# Nguon3V.net
KiCad netlist of a schematic drawn in Altium Designer
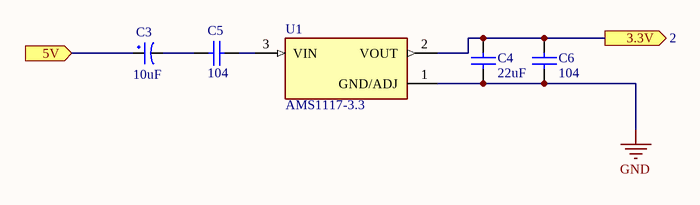
[diagram p0: Nguon3V.SchDoc]

(export (version "E")
  (design (tool "Eeschema 10.0.6"))
  (components
    (comp (ref "C3")
      (value "10uF")
      (footprint "tu hoa 4mm")
      (description "Cắm")
      (libsource (lib "Altium_Lib_by_KhueNguyenCreator") (part "Tu Hoa 10uF 16V 4x7"))
    )
    (comp (ref "C4")
      (value "22uF")
      (footprint "tu tantalum dip5.08")
      (description "Cắm")
      (libsource (lib "Altium_Lib_by_KhueNguyenCreator") (part "Tu tantalum 0.22uF 50V DIP5.08"))
    )
    (comp (ref "C5")
      (value "104")
      (footprint "tu gom")
      (description "Cắm")
      (libsource (lib "Altium_Lib_by_KhueNguyenCreator") (part "Tu gom 104 50V"))
    )
    (comp (ref "C6")
      (value "104")
      (footprint "tu gom")
      (description "Cắm")
      (libsource (lib "Altium_Lib_by_KhueNguyenCreator") (part "Tu gom 104 50V"))
    )
    (comp (ref "U1")
      (value "AMS1117-3.3")
      (footprint "SOT229P700X180-4N")
      (description "Sot223/Pkg 1-Amp 3.3-Volt Low Drop Out Voltage Regulatator")
      (fields (field (name "MF") "Advanced Monolithic Systems"))
      (libsource (lib "AMS1117-3.3") (part "AMS1117-3.3"))
    )
  )
  (nets
    (net (code "1") (name "/3.3V") (class "Default")
      (node (ref "C4") (pin "1") (pinfunction "1_1") (pintype "passive"))
      (node (ref "C6") (pin "1") (pinfunction "1_1") (pintype "passive"))
      (node (ref "U1") (pin "2") (pinfunction "VOUT_2") (pintype "output"))
    )
    (net (code "2") (name "/5V") (class "Default")
      (node (ref "C3") (pin "1") (pinfunction "1_1") (pintype "passive"))
    )
    (net (code "3") (name "GND") (class "Default")
      (node (ref "C4") (pin "2") (pinfunction "2_2") (pintype "passive"))
      (node (ref "C6") (pin "2") (pinfunction "2_2") (pintype "passive"))
      (node (ref "U1") (pin "1") (pinfunction "GND/ADJ_1") (pintype "power_in"))
    )
    (net (code "4") (name "Net-(C3-Pad2)") (class "Default")
      (node (ref "C3") (pin "2") (pinfunction "2_2") (pintype "passive"))
      (node (ref "C5") (pin "2") (pinfunction "2_2") (pintype "passive"))
    )
    (net (code "5") (name "Net-(U1-VIN)") (class "Default")
      (node (ref "C5") (pin "1") (pinfunction "1_1") (pintype "passive"))
      (node (ref "U1") (pin "3") (pinfunction "VIN_3") (pintype "input"))
    )
  )
)
